# EPS_DCDC_RLCL-FPF.net
KiCad netlist of a schematic drawn in Altium Designer
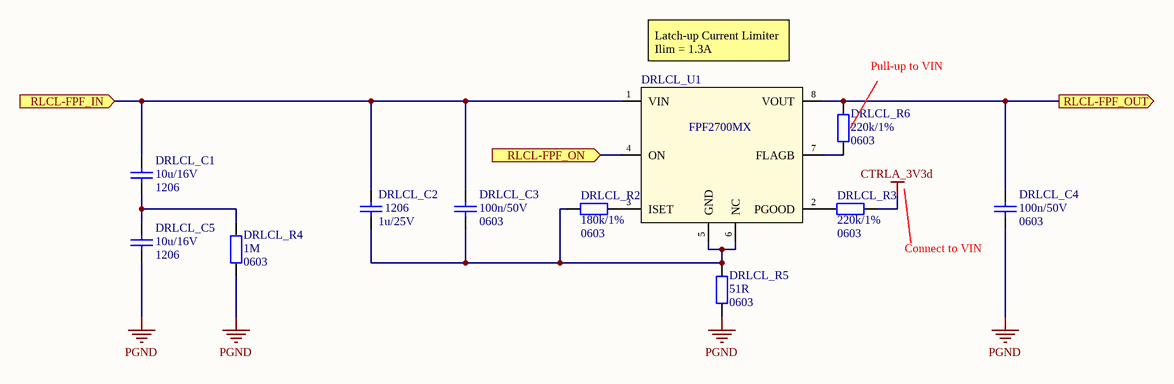
[diagram p0: EPS_DCDC_RLCL-FPF.SchDoc]

(export (version "E")
  (design (tool "Eeschema 10.0.6"))
  (components
    (comp (ref "DRLCL_C1")
      (value "10u/16V")
      (footprint "SMD_Capacitor_1206")
      (description "Ceramic Cap Kemet COTS 10u/16V X7R 1206")
      (fields
        (field (name "MANUFACTURERPARTNUMBER") "C1206T106K4RACTU")
        (field (name "MANUFACTURER") "Kemet")
        (field (name "PACKGE") "1206")
      )
      (libsource (lib "capacitors") (part "Cer_C1206T106K4RACTU"))
    )
    (comp (ref "DRLCL_C2")
      (value "1u/25V")
      (footprint "SMD_Capacitor_1206")
      (description "Ceramic Cap Kemet COTS 1u/25V X7R 1206")
      (fields
        (field (name "MANUFACTURERPARTNUMBER") "C1206T105K3RALTU")
        (field (name "MANUFACTURER") "Kemet")
        (field (name "PACKAGE") "1206")
      )
      (libsource (lib "capacitors") (part "Cer_C1206T105K3RALTU"))
    )
    (comp (ref "DRLCL_C3")
      (value "100n/50V")
      (footprint "SMD_Capacitor_0603")
      (description "Ceramic Cap Murata Automotive 100n/50V X7R 0603")
      (fields
        (field (name "MANUFACTURER") "Murata")
        (field (name "MANUFACTURERPARTNUMBER") "GCJ188R71H104KA12D")
        (field (name "PACKAGE") "0603")
      )
      (libsource (lib "capacitors") (part "Cer_GCJ188R71H104KA12D"))
    )
    (comp (ref "DRLCL_C4")
      (value "100n/50V")
      (footprint "SMD_Capacitor_0603")
      (description "Ceramic Cap Murata Automotive 100n/50V X7R 0603")
      (fields
        (field (name "MANUFACTURER") "Murata")
        (field (name "MANUFACTURERPARTNUMBER") "GCJ188R71H104KA12D")
        (field (name "PACKAGE") "0603")
      )
      (libsource (lib "capacitors") (part "Cer_GCJ188R71H104KA12D"))
    )
    (comp (ref "DRLCL_C5")
      (value "10u/16V")
      (footprint "SMD_Capacitor_1206")
      (description "Ceramic Cap Kemet COTS 10u/16V X7R 1206")
      (fields
        (field (name "MANUFACTURERPARTNUMBER") "C1206T106K4RACTU")
        (field (name "MANUFACTURER") "Kemet")
        (field (name "PACKGE") "1206")
      )
      (libsource (lib "capacitors") (part "Cer_C1206T106K4RACTU"))
    )
    (comp (ref "DRLCL_R2")
      (value "180k/1%")
      (footprint "SMD_Resistor_0603")
      (fields (field (name "PACKAGE") "0603"))
      (libsource (lib "") (part "Res_2"))
    )
    (comp (ref "DRLCL_R3")
      (value "220k/1%")
      (footprint "SMD_Resistor_0603")
      (fields (field (name "PACKAGE") "0603"))
      (libsource (lib "") (part "Res_2"))
    )
    (comp (ref "DRLCL_R4")
      (value "1M")
      (footprint "SMD_Resistor_0603")
      (fields (field (name "PACKAGE") "0603"))
      (libsource (lib "resistors") (part "Res"))
    )
    (comp (ref "DRLCL_R5")
      (value "51R")
      (footprint "SMD_Resistor_0603")
      (fields (field (name "PACKAGE") "0603"))
      (libsource (lib "") (part "Res_1"))
    )
    (comp (ref "DRLCL_R6")
      (value "220k/1%")
      (footprint "SMD_Resistor_0603")
      (fields (field (name "PACKAGE") "0603"))
      (libsource (lib "resistors") (part "Res"))
    )
    (comp (ref "DRLCL_U1")
      (value "FPF2700MX")
      (footprint "SOIC-8-N")
      (description "Adj over-current protection 0.4-2A, Load Switch")
      (fields (field (name "MANUFACTURER") "Fairchild Semiconductor"))
      (libsource (lib "microcircuits") (part "FPF2700MX"))
    )
  )
  (nets
    (net (code "1") (name "/RLCL-FPF_IN") (class "Default")
      (node (ref "DRLCL_C1") (pin "1") (pinfunction "1_1") (pintype "passive"))
      (node (ref "DRLCL_C2") (pin "1") (pinfunction "1_1") (pintype "passive"))
      (node (ref "DRLCL_C3") (pin "1") (pinfunction "1_1") (pintype "passive"))
      (node (ref "DRLCL_U1") (pin "1") (pinfunction "VIN_1") (pintype "passive"))
    )
    (net (code "2") (name "/RLCL-FPF_ON") (class "Default")
      (node (ref "DRLCL_U1") (pin "4") (pinfunction "ON_4") (pintype "passive"))
    )
    (net (code "3") (name "/RLCL-FPF_OUT") (class "Default")
      (node (ref "DRLCL_C4") (pin "1") (pinfunction "1_1") (pintype "passive"))
      (node (ref "DRLCL_R6") (pin "2") (pinfunction "2_2") (pintype "passive"))
      (node (ref "DRLCL_U1") (pin "8") (pinfunction "VOUT_8") (pintype "passive"))
    )
    (net (code "4") (name "CTRLA_3V3d") (class "Default")
      (node (ref "DRLCL_R3") (pin "2") (pinfunction "2_2") (pintype "passive"))
    )
    (net (code "5") (name "Net-(DRLCL_C1-Pad2)") (class "Default")
      (node (ref "DRLCL_C1") (pin "2") (pinfunction "2_2") (pintype "passive"))
      (node (ref "DRLCL_C5") (pin "1") (pinfunction "1_1") (pintype "passive"))
      (node (ref "DRLCL_R4") (pin "2") (pinfunction "2_2") (pintype "passive"))
    )
    (net (code "6") (name "Net-(DRLCL_U1-FLAGB)") (class "Default")
      (node (ref "DRLCL_R6") (pin "1") (pinfunction "1_1") (pintype "passive"))
      (node (ref "DRLCL_U1") (pin "7") (pinfunction "FLAGB_7") (pintype "passive"))
    )
    (net (code "7") (name "Net-(DRLCL_U1-GND)") (class "Default")
      (node (ref "DRLCL_C2") (pin "2") (pinfunction "2_2") (pintype "passive"))
      (node (ref "DRLCL_C3") (pin "2") (pinfunction "2_2") (pintype "passive"))
      (node (ref "DRLCL_R2") (pin "1") (pinfunction "1_1") (pintype "passive"))
      (node (ref "DRLCL_R5") (pin "1") (pinfunction "1_1") (pintype "passive"))
      (node (ref "DRLCL_U1") (pin "5") (pinfunction "GND_5") (pintype "passive"))
      (node (ref "DRLCL_U1") (pin "6") (pinfunction "NC_6") (pintype "passive"))
    )
    (net (code "8") (name "Net-(DRLCL_U1-ISET)") (class "Default")
      (node (ref "DRLCL_R2") (pin "2") (pinfunction "2_2") (pintype "passive"))
      (node (ref "DRLCL_U1") (pin "3") (pinfunction "ISET_3") (pintype "passive"))
    )
    (net (code "9") (name "Net-(DRLCL_U1-PGOOD)") (class "Default")
      (node (ref "DRLCL_R3") (pin "1") (pinfunction "1_1") (pintype "passive"))
      (node (ref "DRLCL_U1") (pin "2") (pinfunction "PGOOD_2") (pintype "passive"))
    )
    (net (code "10") (name "PGND") (class "Default")
      (node (ref "DRLCL_C4") (pin "2") (pinfunction "2_2") (pintype "passive"))
      (node (ref "DRLCL_C5") (pin "2") (pinfunction "2_2") (pintype "passive"))
      (node (ref "DRLCL_R4") (pin "1") (pinfunction "1_1") (pintype "passive"))
      (node (ref "DRLCL_R5") (pin "2") (pinfunction "2_2") (pintype "passive"))
    )
  )
)
